# USB_MUX.net
KiCad netlist of a schematic drawn in Altium Designer
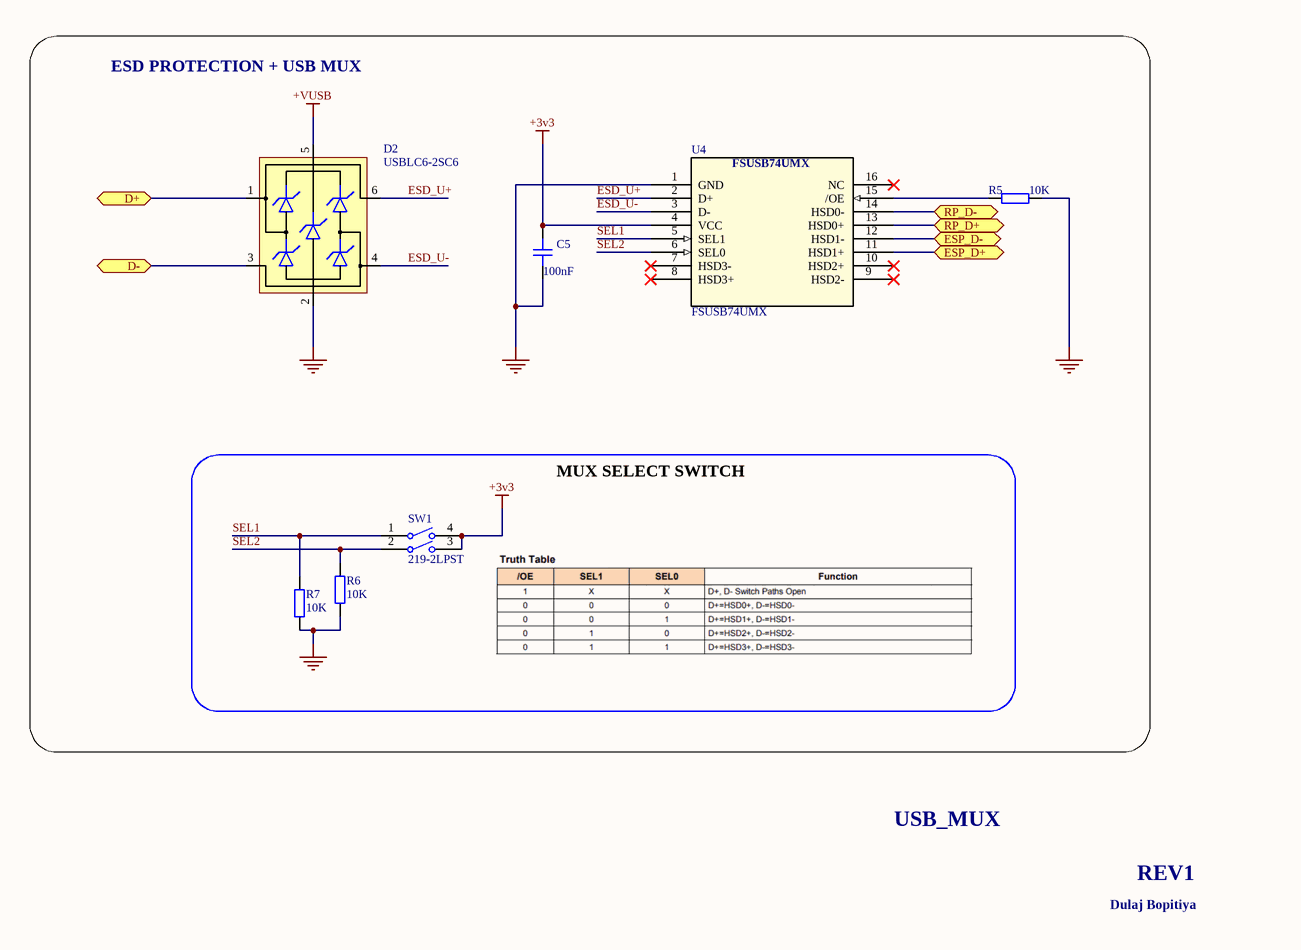
[diagram p0: USB MUX.SchDoc, left]

(export (version "E")
  (design (tool "Eeschema 10.0.6"))
  (components
    (comp (ref "C5")
      (value "100nF")
      (footprint "CAP_0603")
      (description "Capacitor SMD 0603")
      (libsource (lib "Schematic-Lib-PhilsLab") (part "CAP_0603"))
    )
    (comp (ref "D2")
      (value "USBLC6-2SC6")
      (footprint "SOT-23-6")
      (description "Low-Capacitance ESD Protection USB")
      (fields (field (name "MANUFACTURER") "STMicroelectronics"))
      (libsource (lib "Schematic-Lib-PhilsLab") (part "USBLC6-2SC6"))
    )
    (comp (ref "R5")
      (value "10K")
      (footprint "RES_0603")
      (description "Resistor SMD 0603")
      (libsource (lib "Schematic-Lib-PhilsLab") (part "RES_0603"))
    )
    (comp (ref "R6")
      (value "10K")
      (footprint "RES_0603")
      (description "Resistor SMD 0603")
      (libsource (lib "Schematic-Lib-PhilsLab") (part "RES_0603"))
    )
    (comp (ref "R7")
      (value "10K")
      (footprint "RES_0603")
      (description "Resistor SMD 0603")
      (libsource (lib "Schematic-Lib-PhilsLab") (part "RES_0603"))
    )
    (comp (ref "SW1")
      (value "219-2LPST")
      (footprint "CTS-219-2LPST_V")
      (description "Surface Mount DIP Switch Auto Placeable, -55 to 85 degC, 4-Pin SMD, RoHS, Tube")
      (fields (field (name "MANUFACTURER") "CTS Corporation"))
      (libsource (lib "Altium Content Vault") (part "SW-SPST-4_C"))
    )
    (comp (ref "U4")
      (value "FSUSB74UMX")
      (footprint "FSUSB74UMX:UMLP16_1P8X2P6_ONS")
      (description "No Description Available")
      (fields (field (name "COPYRIGHT") "Copyright (C) 2025 Ultra Librarian. All rights reserved."))
      (libsource (lib "FSUSB74UMX") (part "FSUSB74UMX"))
    )
  )
  (nets
    (net (code "1") (name "+3v3") (class "Default")
      (node (ref "C5") (pin "2") (pinfunction "2_2") (pintype "passive"))
      (node (ref "SW1") (pin "3") (pinfunction "3_3") (pintype "passive"))
      (node (ref "SW1") (pin "4") (pinfunction "4_4") (pintype "passive"))
      (node (ref "U4") (pin "4") (pinfunction "VCC_4") (pintype "power_in"))
    )
    (net (code "2") (name "+VUSB") (class "Default")
      (node (ref "D2") (pin "5") (pinfunction "VBUS_5") (pintype "power_in"))
    )
    (net (code "3") (name "/D+") (class "Default")
      (node (ref "D2") (pin "1") (pinfunction "IO1_1") (pintype "bidirectional"))
    )
    (net (code "4") (name "/D-") (class "Default")
      (node (ref "D2") (pin "3") (pinfunction "IO2_3") (pintype "bidirectional"))
    )
    (net (code "5") (name "/ESD_U+") (class "Default")
      (node (ref "D2") (pin "6") (pinfunction "IO1_6") (pintype "bidirectional"))
      (node (ref "U4") (pin "2") (pinfunction "D+_2") (pintype "passive"))
    )
    (net (code "6") (name "/ESD_U-") (class "Default")
      (node (ref "D2") (pin "4") (pinfunction "IO2_4") (pintype "bidirectional"))
      (node (ref "U4") (pin "3") (pinfunction "D-_3") (pintype "passive"))
    )
    (net (code "7") (name "/ESP_D+") (class "Default")
      (node (ref "U4") (pin "11") (pinfunction "HSD1+_11") (pintype "passive"))
    )
    (net (code "8") (name "/ESP_D-") (class "Default")
      (node (ref "U4") (pin "12") (pinfunction "HSD1-_12") (pintype "passive"))
    )
    (net (code "9") (name "/RP_D+") (class "Default")
      (node (ref "U4") (pin "13") (pinfunction "HSD0+_13") (pintype "passive"))
    )
    (net (code "10") (name "/RP_D-") (class "Default")
      (node (ref "U4") (pin "14") (pinfunction "HSD0-_14") (pintype "passive"))
    )
    (net (code "11") (name "/SEL1") (class "Default")
      (node (ref "R7") (pin "2") (pinfunction "2_2") (pintype "passive"))
      (node (ref "SW1") (pin "1") (pinfunction "1_1") (pintype "passive"))
      (node (ref "U4") (pin "5") (pinfunction "SEL1_5") (pintype "input"))
    )
    (net (code "12") (name "/SEL2") (class "Default")
      (node (ref "R6") (pin "2") (pinfunction "2_2") (pintype "passive"))
      (node (ref "SW1") (pin "2") (pinfunction "2_2") (pintype "passive"))
      (node (ref "U4") (pin "6") (pinfunction "SEL0_6") (pintype "input"))
    )
    (net (code "13") (name "GND") (class "Default")
      (node (ref "C5") (pin "1") (pinfunction "1_1") (pintype "passive"))
      (node (ref "D2") (pin "2") (pinfunction "GND_2") (pintype "power_in"))
      (node (ref "R5") (pin "1") (pinfunction "1_1") (pintype "passive"))
      (node (ref "R6") (pin "1") (pinfunction "1_1") (pintype "passive"))
      (node (ref "R7") (pin "1") (pinfunction "1_1") (pintype "passive"))
      (node (ref "U4") (pin "1") (pinfunction "GND_1") (pintype "power_in"))
    )
    (net (code "14") (name "Net-(U4-{slash}OE)") (class "Default")
      (node (ref "R5") (pin "2") (pinfunction "2_2") (pintype "passive"))
      (node (ref "U4") (pin "15") (pinfunction "/OE_15") (pintype "input"))
    )
    (net (code "15") (name "unconnected-(U4-HSD2+-Pad10)") (class "Default")
      (node (ref "U4") (pin "10") (pinfunction "HSD2+_10") (pintype "passive+no_connect"))
    )
    (net (code "16") (name "unconnected-(U4-HSD2--Pad9)") (class "Default")
      (node (ref "U4") (pin "9") (pinfunction "HSD2-_9") (pintype "passive+no_connect"))
    )
    (net (code "17") (name "unconnected-(U4-HSD3+-Pad8)") (class "Default")
      (node (ref "U4") (pin "8") (pinfunction "HSD3+_8") (pintype "passive+no_connect"))
    )
    (net (code "18") (name "unconnected-(U4-HSD3--Pad7)") (class "Default")
      (node (ref "U4") (pin "7") (pinfunction "HSD3-_7") (pintype "passive+no_connect"))
    )
    (net (code "19") (name "unconnected-(U4-NC-Pad16)") (class "Default")
      (node (ref "U4") (pin "16") (pinfunction "NC_16") (pintype "passive+no_connect"))
    )
  )
)
